# QSPI_Memory.net
KiCad netlist of a schematic drawn in Altium Designer
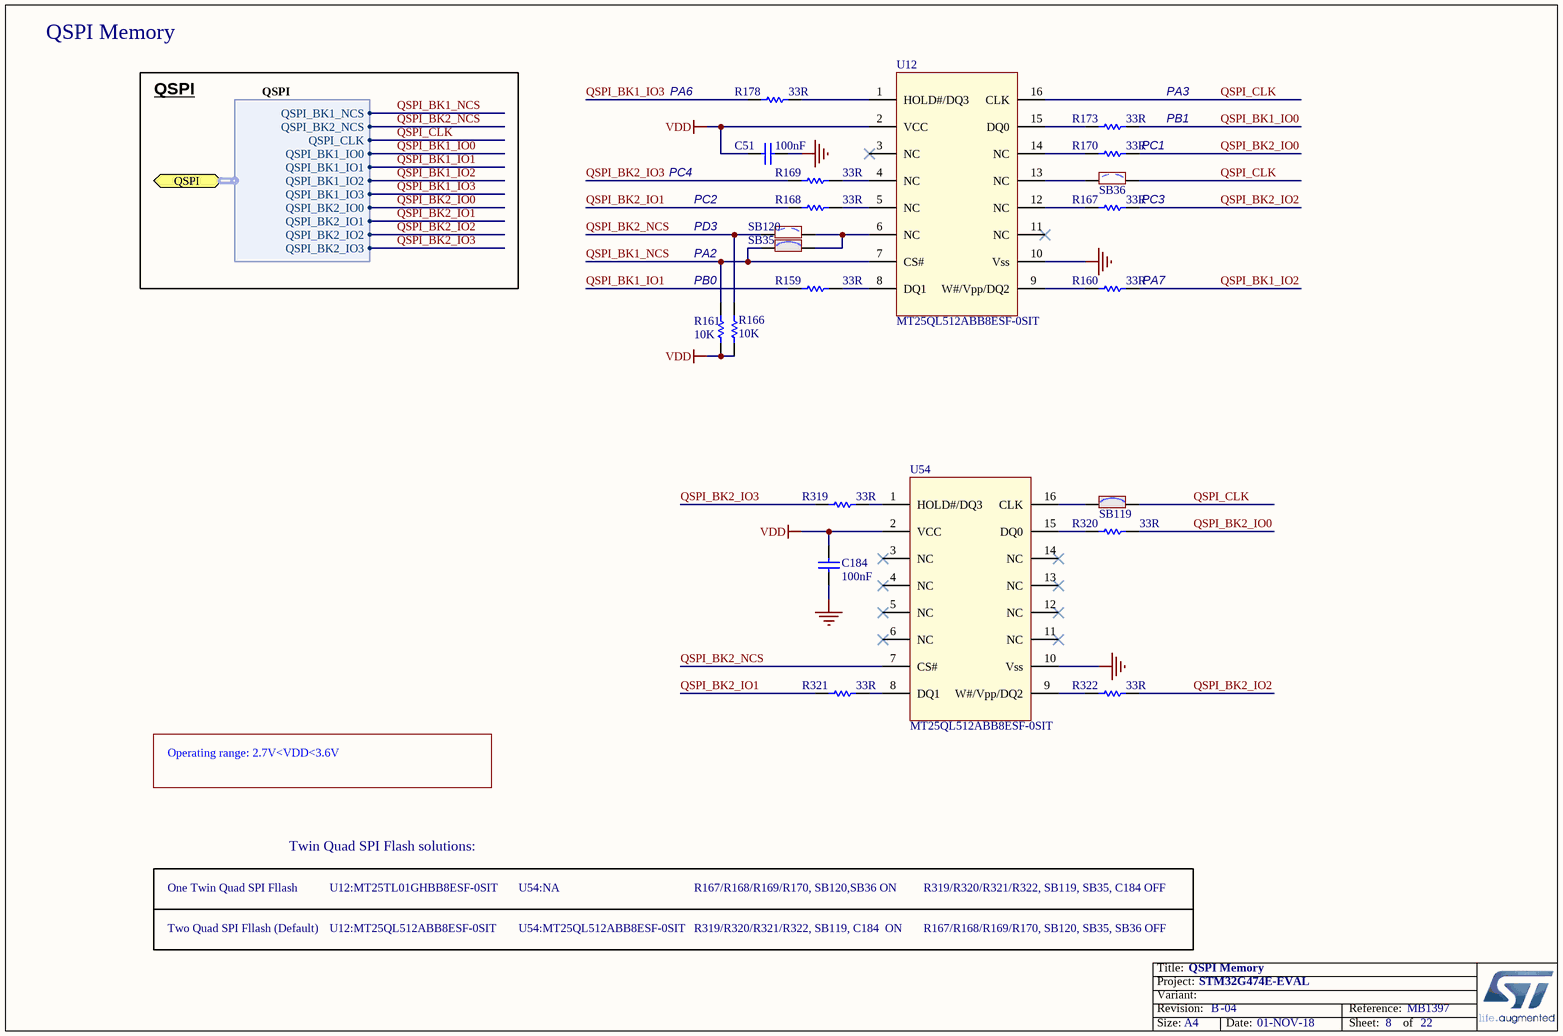
[diagram p0: QSPI Memory.SchDoc]

(export (version "E")
  (design (tool "Eeschema 10.0.6"))
  (components
    (comp (ref "C51")
      (value "100nF")
      (footprint "C0402")
      (description "Capacitor, MLCC, 100nF, 16V, X7R, 10%, 0402, T=0.5mm")
      (fields
        (field (name "INTERNAL_PART_NUMBER") "MCD-00006")
        (field (name "MANUFACTURER_PART_NUMBER") "CC0402KRX7R7BB104")
        (field (name "PROVIDED_BY") "SUBCO")
      )
      (libsource (lib "MCD_PARTS_database") (part "Capacitor"))
    )
    (comp (ref "C184")
      (value "100nF")
      (footprint "C0402")
      (description "Capacitor, MLCC, 100nF, 16V, X7R, 10%, 0402, T=0.5mm")
      (fields
        (field (name "INTERNAL_PART_NUMBER") "MCD-00006")
        (field (name "MANUFACTURER_PART_NUMBER") "CC0402KRX7R7BB104")
        (field (name "PROVIDED_BY") "SUBCO")
      )
      (libsource (lib "MCD_PARTS_database") (part "Capacitor"))
    )
    (comp (ref "R159")
      (value "33R")
      (footprint "R0402")
      (description "Resistor,33R,0402,1%,1/16W")
      (fields
        (field (name "INTERNAL_PART_NUMBER") "MCD-00455")
        (field (name "MANUFACTURER_PART_NUMBER") "RC0402FR-0733RL")
        (field (name "PROVIDED_BY") "SUBCO")
      )
      (libsource (lib "MCD_PARTS_database") (part "Resistor"))
    )
    (comp (ref "R160")
      (value "33R")
      (footprint "R0402")
      (description "Resistor,33R,0402,1%,1/16W")
      (fields
        (field (name "INTERNAL_PART_NUMBER") "MCD-00455")
        (field (name "MANUFACTURER_PART_NUMBER") "RC0402FR-0733RL")
        (field (name "PROVIDED_BY") "SUBCO")
      )
      (libsource (lib "MCD_PARTS_database") (part "Resistor"))
    )
    (comp (ref "R161")
      (value "10K")
      (footprint "R0402")
      (description "Resistor,10K,0402,1%,1/16W")
      (fields
        (field (name "INTERNAL_PART_NUMBER") "MCD-00053")
        (field (name "MANUFACTURER_PART_NUMBER") "RC0402FR-0710KL")
        (field (name "PROVIDED_BY") "SUBCO")
      )
      (libsource (lib "MCD_PARTS_database") (part "Resistor"))
    )
    (comp (ref "R166")
      (value "10K")
      (footprint "R0402")
      (description "Resistor,10K,0402,1%,1/16W")
      (fields
        (field (name "INTERNAL_PART_NUMBER") "MCD-00053")
        (field (name "MANUFACTURER_PART_NUMBER") "RC0402FR-0710KL")
        (field (name "PROVIDED_BY") "SUBCO")
      )
      (libsource (lib "MCD_PARTS_database") (part "Resistor"))
    )
    (comp (ref "R167")
      (value "33R")
      (footprint "R0402")
      (description "Resistor,33R,0402,1%,1/16W")
      (fields
        (field (name "INTERNAL_PART_NUMBER") "MCD-00455")
        (field (name "MANUFACTURER_PART_NUMBER") "RC0402FR-0733RL")
        (field (name "PROVIDED_BY") "SUBCO")
      )
      (libsource (lib "MCD_PARTS_database") (part "Resistor"))
    )
    (comp (ref "R168")
      (value "33R")
      (footprint "R0402")
      (description "Resistor,33R,0402,1%,1/16W")
      (fields
        (field (name "INTERNAL_PART_NUMBER") "MCD-00455")
        (field (name "MANUFACTURER_PART_NUMBER") "RC0402FR-0733RL")
        (field (name "PROVIDED_BY") "SUBCO")
      )
      (libsource (lib "MCD_PARTS_database") (part "Resistor"))
    )
    (comp (ref "R169")
      (value "33R")
      (footprint "R0402")
      (description "Resistor,33R,0402,1%,1/16W")
      (fields
        (field (name "INTERNAL_PART_NUMBER") "MCD-00455")
        (field (name "MANUFACTURER_PART_NUMBER") "RC0402FR-0733RL")
        (field (name "PROVIDED_BY") "SUBCO")
      )
      (libsource (lib "MCD_PARTS_database") (part "Resistor"))
    )
    (comp (ref "R170")
      (value "33R")
      (footprint "R0402")
      (description "Resistor,33R,0402,1%,1/16W")
      (fields
        (field (name "INTERNAL_PART_NUMBER") "MCD-00455")
        (field (name "MANUFACTURER_PART_NUMBER") "RC0402FR-0733RL")
        (field (name "PROVIDED_BY") "SUBCO")
      )
      (libsource (lib "MCD_PARTS_database") (part "Resistor"))
    )
    (comp (ref "R173")
      (value "33R")
      (footprint "R0402")
      (description "Resistor,33R,0402,1%,1/16W")
      (fields
        (field (name "INTERNAL_PART_NUMBER") "MCD-00455")
        (field (name "MANUFACTURER_PART_NUMBER") "RC0402FR-0733RL")
        (field (name "PROVIDED_BY") "SUBCO")
      )
      (libsource (lib "MCD_PARTS_database") (part "Resistor"))
    )
    (comp (ref "R178")
      (value "33R")
      (footprint "R0402")
      (description "Resistor,33R,0402,1%,1/16W")
      (fields
        (field (name "INTERNAL_PART_NUMBER") "MCD-00455")
        (field (name "MANUFACTURER_PART_NUMBER") "RC0402FR-0733RL")
        (field (name "PROVIDED_BY") "SUBCO")
      )
      (libsource (lib "MCD_PARTS_database") (part "Resistor"))
    )
    (comp (ref "R319")
      (value "33R")
      (footprint "R0402")
      (description "Resistor,33R,0402,1%,1/16W")
      (fields
        (field (name "INTERNAL_PART_NUMBER") "MCD-00455")
        (field (name "MANUFACTURER_PART_NUMBER") "RC0402FR-0733RL")
        (field (name "PROVIDED_BY") "SUBCO")
      )
      (libsource (lib "MCD_PARTS_database") (part "Resistor"))
    )
    (comp (ref "R320")
      (value "33R")
      (footprint "R0402")
      (description "Resistor,33R,0402,1%,1/16W")
      (fields
        (field (name "INTERNAL_PART_NUMBER") "MCD-00455")
        (field (name "MANUFACTURER_PART_NUMBER") "RC0402FR-0733RL")
        (field (name "PROVIDED_BY") "SUBCO")
      )
      (libsource (lib "MCD_PARTS_database") (part "Resistor"))
    )
    (comp (ref "R321")
      (value "33R")
      (footprint "R0402")
      (description "Resistor,33R,0402,1%,1/16W")
      (fields
        (field (name "INTERNAL_PART_NUMBER") "MCD-00455")
        (field (name "MANUFACTURER_PART_NUMBER") "RC0402FR-0733RL")
        (field (name "PROVIDED_BY") "SUBCO")
      )
      (libsource (lib "MCD_PARTS_database") (part "Resistor"))
    )
    (comp (ref "R322")
      (value "33R")
      (footprint "R0402")
      (description "Resistor,33R,0402,1%,1/16W")
      (fields
        (field (name "INTERNAL_PART_NUMBER") "MCD-00455")
        (field (name "MANUFACTURER_PART_NUMBER") "RC0402FR-0733RL")
        (field (name "PROVIDED_BY") "SUBCO")
      )
      (libsource (lib "MCD_PARTS_database") (part "Resistor"))
    )
    (comp (ref "SB35")
      (value "SB_ON")
      (footprint "SOLDER-BRIDGE_R0603-0R")
      (description "Solder Bridge ON")
      (fields
        (field (name "INTERNAL_PART_NUMBER") "MCD-00071")
        (field (name "MANUFACTURER_PART_NUMBER") "RC0603JR-070RL")
        (field (name "PROVIDED_BY") "SUBCO")
      )
      (libsource (lib "MCD_PARTS_database") (part "SB_ON"))
    )
    (comp (ref "SB36")
      (value "SB_OFF")
      (footprint "SOLDER-BRIDGE_R0603-0R")
      (description "Solder Bridge OFF")
      (fields
        (field (name "INTERNAL_PART_NUMBER") "MCD-00072")
        (field (name "MANUFACTURER_PART_NUMBER") "RC0603JR-070RL")
        (field (name "PROVIDED_BY") "SUBCO")
      )
      (libsource (lib "MCD_PARTS_database") (part "SB_OFF"))
    )
    (comp (ref "SB119")
      (value "SB_ON")
      (footprint "SOLDER-BRIDGE_R0603-0R")
      (description "Solder Bridge ON")
      (fields
        (field (name "INTERNAL_PART_NUMBER") "MCD-00071")
        (field (name "MANUFACTURER_PART_NUMBER") "RC0603JR-070RL")
        (field (name "PROVIDED_BY") "SUBCO")
      )
      (libsource (lib "MCD_PARTS_database") (part "SB_ON"))
    )
    (comp (ref "SB120")
      (value "SB_OFF")
      (footprint "SOLDER-BRIDGE_R0603-0R")
      (description "Solder Bridge OFF")
      (fields
        (field (name "INTERNAL_PART_NUMBER") "MCD-00072")
        (field (name "MANUFACTURER_PART_NUMBER") "RC0603JR-070RL")
        (field (name "PROVIDED_BY") "SUBCO")
      )
      (libsource (lib "MCD_PARTS_database") (part "SB_OFF"))
    )
    (comp (ref "U12")
      (value "MT25QL512ABB8ESF-0SIT")
      (footprint "ICC_SOP2-SF_16P_10P3X7P5_P127")
      (description "Micron Serial NOR Flash Memory")
      (fields
        (field (name "INTERNAL_PART_NUMBER") "MCD-01128")
        (field (name "MANUFACTURER") "MICRON")
        (field (name "PROVIDED_BY") "SUBCO")
      )
      (libsource (lib "MCD_PARTS_database") (part "MT25QL512ABB8ESF-0SIT"))
    )
    (comp (ref "U54")
      (value "MT25QL512ABB8ESF-0SIT")
      (footprint "ICC_SOP2-SF_16P_10P3X7P5_P127")
      (description "Micron Serial NOR Flash Memory")
      (fields
        (field (name "INTERNAL_PART_NUMBER") "MCD-01128")
        (field (name "MANUFACTURER") "MICRON")
        (field (name "PROVIDED_BY") "SUBCO")
      )
      (libsource (lib "MCD_PARTS_database") (part "MT25QL512ABB8ESF-0SIT"))
    )
  )
  (nets
    (net (code "2") (name "/QSPI_BK1_IO0") (class "Default")
      (node (ref "R173") (pin "2") (pinfunction "2_2") (pintype "passive"))
    )
    (net (code "3") (name "/QSPI_BK1_IO1") (class "Default")
      (node (ref "R159") (pin "1") (pinfunction "1_1") (pintype "passive"))
    )
    (net (code "4") (name "/QSPI_BK1_IO2") (class "Default")
      (node (ref "R160") (pin "2") (pinfunction "2_2") (pintype "passive"))
    )
    (net (code "5") (name "/QSPI_BK1_IO3") (class "Default")
      (node (ref "R178") (pin "1") (pinfunction "1_1") (pintype "passive"))
    )
    (net (code "6") (name "/QSPI_BK1_NCS") (class "Default")
      (node (ref "R161") (pin "2") (pinfunction "2_2") (pintype "passive"))
      (node (ref "SB35") (pin "1") (pinfunction "1_1") (pintype "passive"))
      (node (ref "U12") (pin "7") (pinfunction "CS#_7") (pintype "passive"))
    )
    (net (code "7") (name "/QSPI_BK2_IO0") (class "Default")
      (node (ref "R170") (pin "2") (pinfunction "2_2") (pintype "passive"))
      (node (ref "R320") (pin "2") (pinfunction "2_2") (pintype "passive"))
    )
    (net (code "8") (name "/QSPI_BK2_IO1") (class "Default")
      (node (ref "R168") (pin "1") (pinfunction "1_1") (pintype "passive"))
      (node (ref "R321") (pin "1") (pinfunction "1_1") (pintype "passive"))
    )
    (net (code "9") (name "/QSPI_BK2_IO2") (class "Default")
      (node (ref "R167") (pin "2") (pinfunction "2_2") (pintype "passive"))
      (node (ref "R322") (pin "2") (pinfunction "2_2") (pintype "passive"))
    )
    (net (code "10") (name "/QSPI_BK2_IO3") (class "Default")
      (node (ref "R169") (pin "1") (pinfunction "1_1") (pintype "passive"))
      (node (ref "R319") (pin "1") (pinfunction "1_1") (pintype "passive"))
    )
    (net (code "11") (name "/QSPI_BK2_NCS") (class "Default")
      (node (ref "R166") (pin "2") (pinfunction "2_2") (pintype "passive"))
      (node (ref "SB120") (pin "1") (pinfunction "1_1") (pintype "passive"))
      (node (ref "U54") (pin "7") (pinfunction "CS#_7") (pintype "passive"))
    )
    (net (code "12") (name "/QSPI_CLK") (class "Default")
      (node (ref "SB119") (pin "2") (pinfunction "2_2") (pintype "passive"))
      (node (ref "SB36") (pin "2") (pinfunction "2_2") (pintype "passive"))
      (node (ref "U12") (pin "16") (pinfunction "CLK_16") (pintype "passive"))
    )
    (net (code "14") (name "GND") (class "Default")
      (node (ref "C184") (pin "1") (pinfunction "1_1") (pintype "passive"))
      (node (ref "C51") (pin "1") (pinfunction "1_1") (pintype "passive"))
      (node (ref "U12") (pin "10") (pinfunction "Vss_10") (pintype "passive"))
      (node (ref "U54") (pin "10") (pinfunction "Vss_10") (pintype "passive"))
    )
    (net (code "15") (name "Net-(R167-Pad1)") (class "Default")
      (node (ref "R167") (pin "1") (pinfunction "1_1") (pintype "passive"))
      (node (ref "U12") (pin "12") (pinfunction "NC_12") (pintype "passive"))
    )
    (net (code "16") (name "Net-(R168-Pad2)") (class "Default")
      (node (ref "R168") (pin "2") (pinfunction "2_2") (pintype "passive"))
      (node (ref "U12") (pin "5") (pinfunction "NC_5") (pintype "passive"))
    )
    (net (code "17") (name "Net-(R169-Pad2)") (class "Default")
      (node (ref "R169") (pin "2") (pinfunction "2_2") (pintype "passive"))
      (node (ref "U12") (pin "4") (pinfunction "NC_4") (pintype "passive"))
    )
    (net (code "18") (name "Net-(R170-Pad1)") (class "Default")
      (node (ref "R170") (pin "1") (pinfunction "1_1") (pintype "passive"))
      (node (ref "U12") (pin "14") (pinfunction "NC_14") (pintype "passive"))
    )
    (net (code "19") (name "Net-(SB36-Pad1)") (class "Default")
      (node (ref "SB36") (pin "1") (pinfunction "1_1") (pintype "passive"))
      (node (ref "U12") (pin "13") (pinfunction "NC_13") (pintype "passive"))
    )
    (net (code "20") (name "Net-(SB120-Pad2)") (class "Default")
      (node (ref "SB120") (pin "2") (pinfunction "2_2") (pintype "passive"))
      (node (ref "SB35") (pin "2") (pinfunction "2_2") (pintype "passive"))
      (node (ref "U12") (pin "6") (pinfunction "NC_6") (pintype "passive"))
    )
    (net (code "21") (name "Net-(U12-DQ0)") (class "Default")
      (node (ref "R173") (pin "1") (pinfunction "1_1") (pintype "passive"))
      (node (ref "U12") (pin "15") (pinfunction "DQ0_15") (pintype "passive"))
    )
    (net (code "22") (name "Net-(U12-DQ1)") (class "Default")
      (node (ref "R159") (pin "2") (pinfunction "2_2") (pintype "passive"))
      (node (ref "U12") (pin "8") (pinfunction "DQ1_8") (pintype "passive"))
    )
    (net (code "23") (name "Net-(U12-HOLD#{slash}DQ3)") (class "Default")
      (node (ref "R178") (pin "2") (pinfunction "2_2") (pintype "passive"))
      (node (ref "U12") (pin "1") (pinfunction "HOLD#/DQ3_1") (pintype "passive"))
    )
    (net (code "24") (name "Net-(U12-W#{slash}Vpp{slash}DQ2)") (class "Default")
      (node (ref "R160") (pin "1") (pinfunction "1_1") (pintype "passive"))
      (node (ref "U12") (pin "9") (pinfunction "W#/Vpp/DQ2_9") (pintype "passive"))
    )
    (net (code "25") (name "Net-(U54-CLK)") (class "Default")
      (node (ref "SB119") (pin "1") (pinfunction "1_1") (pintype "passive"))
      (node (ref "U54") (pin "16") (pinfunction "CLK_16") (pintype "passive"))
    )
    (net (code "26") (name "Net-(U54-DQ0)") (class "Default")
      (node (ref "R320") (pin "1") (pinfunction "1_1") (pintype "passive"))
      (node (ref "U54") (pin "15") (pinfunction "DQ0_15") (pintype "passive"))
    )
    (net (code "27") (name "Net-(U54-DQ1)") (class "Default")
      (node (ref "R321") (pin "2") (pinfunction "2_2") (pintype "passive"))
      (node (ref "U54") (pin "8") (pinfunction "DQ1_8") (pintype "passive"))
    )
    (net (code "28") (name "Net-(U54-HOLD#{slash}DQ3)") (class "Default")
      (node (ref "R319") (pin "2") (pinfunction "2_2") (pintype "passive"))
      (node (ref "U54") (pin "1") (pinfunction "HOLD#/DQ3_1") (pintype "passive"))
    )
    (net (code "29") (name "Net-(U54-W#{slash}Vpp{slash}DQ2)") (class "Default")
      (node (ref "R322") (pin "1") (pinfunction "1_1") (pintype "passive"))
      (node (ref "U54") (pin "9") (pinfunction "W#/Vpp/DQ2_9") (pintype "passive"))
    )
    (net (code "30") (name "VDD") (class "Default")
      (node (ref "C184") (pin "2") (pinfunction "2_2") (pintype "passive"))
      (node (ref "C51") (pin "2") (pinfunction "2_2") (pintype "passive"))
      (node (ref "R161") (pin "1") (pinfunction "1_1") (pintype "passive"))
      (node (ref "R166") (pin "1") (pinfunction "1_1") (pintype "passive"))
      (node (ref "U12") (pin "2") (pinfunction "VCC_2") (pintype "passive"))
      (node (ref "U54") (pin "2") (pinfunction "VCC_2") (pintype "passive"))
    )
    (net (code "31") (name "unconnected-(U12-NC-Pad3)") (class "Default")
      (node (ref "U12") (pin "3") (pinfunction "NC_3") (pintype "passive+no_connect"))
    )
    (net (code "32") (name "unconnected-(U12-NC-Pad11)") (class "Default")
      (node (ref "U12") (pin "11") (pinfunction "NC_11") (pintype "passive+no_connect"))
    )
    (net (code "33") (name "unconnected-(U54-NC-Pad3)") (class "Default")
      (node (ref "U54") (pin "3") (pinfunction "NC_3") (pintype "passive+no_connect"))
    )
    (net (code "34") (name "unconnected-(U54-NC-Pad4)") (class "Default")
      (node (ref "U54") (pin "4") (pinfunction "NC_4") (pintype "passive+no_connect"))
    )
    (net (code "35") (name "unconnected-(U54-NC-Pad5)") (class "Default")
      (node (ref "U54") (pin "5") (pinfunction "NC_5") (pintype "passive+no_connect"))
    )
    (net (code "36") (name "unconnected-(U54-NC-Pad6)") (class "Default")
      (node (ref "U54") (pin "6") (pinfunction "NC_6") (pintype "passive+no_connect"))
    )
    (net (code "37") (name "unconnected-(U54-NC-Pad11)") (class "Default")
      (node (ref "U54") (pin "11") (pinfunction "NC_11") (pintype "passive+no_connect"))
    )
    (net (code "38") (name "unconnected-(U54-NC-Pad12)") (class "Default")
      (node (ref "U54") (pin "12") (pinfunction "NC_12") (pintype "passive+no_connect"))
    )
    (net (code "39") (name "unconnected-(U54-NC-Pad13)") (class "Default")
      (node (ref "U54") (pin "13") (pinfunction "NC_13") (pintype "passive+no_connect"))
    )
    (net (code "40") (name "unconnected-(U54-NC-Pad14)") (class "Default")
      (node (ref "U54") (pin "14") (pinfunction "NC_14") (pintype "passive+no_connect"))
    )
  )
)
